# servo.net
KiCad netlist of a schematic drawn in Altium Designer
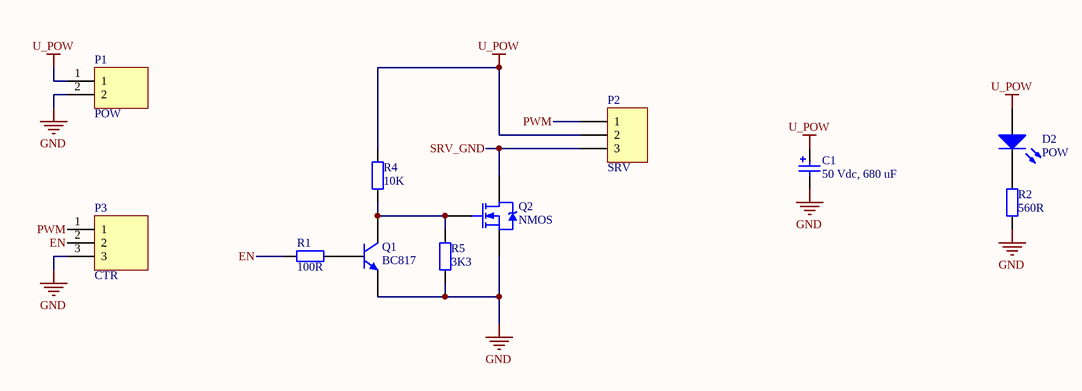
[diagram p0: servo.SchDoc]

(export (version "E")
  (design (tool "Eeschema 10.0.6"))
  (components
    (comp (ref "C1")
      (value "50 Vdc, 680 uF")
      (footprint "WCAP-ATG8_13x20x5")
      (description "WCAP-ATG8 Aluminum Electrolytic Capacitors, 13x20mm, 50 Vdc, 680 uF")
      (fields (field (name "PART NUMBER") "860010678022") (field (name "PUBLISHER") "Wurth Elektronik"))
      (libsource (lib "servo-board") (part "ELKO 860010678022"))
    )
    (comp (ref "D2")
      (value "POW")
      (footprint "FP_0805_LED_RED")
      (description "Typical RED GaAs LED")
      (libsource (lib "hallglib") (part "LED"))
    )
    (comp (ref "P1")
      (value "POW")
      (footprint "FP_CONN2_TAP_254MM_90_EDGE")
      (description "2pin connector")
      (libsource (lib "hallglib") (part "Connector_2pin"))
    )
    (comp (ref "P2")
      (value "SRV")
      (footprint "HDR1X3")
      (description "Header, 3-Pin, Right Angle")
      (fields (field (name "PUBLISHER") "Altium Limited"))
      (libsource (lib "Miscellaneous Connectors") (part "Header 3H"))
    )
    (comp (ref "P3")
      (value "CTR")
      (footprint "FP_CONN3_TAP_254MM_90_EDGE")
      (description "3pin connector")
      (libsource (lib "hallglib") (part "Connector_3pin"))
    )
    (comp (ref "Q1")
      (value "BC817")
      (footprint "FP_SOT23-3")
      (description "NPN General-purpose Transistor")
      (libsource (lib "hallglib") (part "BC817"))
    )
    (comp (ref "Q2") (value "NMOS") (footprint "FP_DPAK-TO252") (libsource (lib "hallglib") (part "NMOS")))
    (comp (ref "R1")
      (value "100R")
      (footprint "FP_0805_RES")
      (description "Resistor")
      (libsource (lib "") (part "RES_1"))
    )
    (comp (ref "R2")
      (value "560R")
      (footprint "FP_0805_RES")
      (description "Resistor")
      (libsource (lib "hallglib") (part "RES"))
    )
    (comp (ref "R4")
      (value "10K")
      (footprint "FP_0805_RES")
      (description "Resistor")
      (libsource (lib "hallglib") (part "RES"))
    )
    (comp (ref "R5")
      (value "3K3")
      (footprint "FP_0805_RES")
      (description "Resistor")
      (libsource (lib "hallglib") (part "RES"))
    )
  )
  (nets
    (net (code "1") (name "/EN") (class "Default")
      (node (ref "P3") (pin "2") (pinfunction "2_2") (pintype "passive"))
      (node (ref "R1") (pin "1") (pinfunction "1_1") (pintype "passive"))
    )
    (net (code "2") (name "/PWM") (class "Default")
      (node (ref "P2") (pin "1") (pinfunction "1_1") (pintype "passive"))
      (node (ref "P3") (pin "1") (pinfunction "1_1") (pintype "passive"))
    )
    (net (code "3") (name "/SRV_GND") (class "Default")
      (node (ref "P2") (pin "3") (pinfunction "3_3") (pintype "passive"))
      (node (ref "Q2") (pin "2") (pinfunction "D_2") (pintype "passive"))
    )
    (net (code "4") (name "GND") (class "Default")
      (node (ref "C1") (pin "2") (pinfunction "N_2") (pintype "passive"))
      (node (ref "P1") (pin "2") (pinfunction "2_2") (pintype "passive"))
      (node (ref "P3") (pin "3") (pinfunction "3_3") (pintype "passive"))
      (node (ref "Q1") (pin "2") (pinfunction "E_2") (pintype "passive"))
      (node (ref "Q2") (pin "3") (pinfunction "S_3") (pintype "passive"))
      (node (ref "R2") (pin "1") (pinfunction "1_1") (pintype "passive"))
      (node (ref "R5") (pin "1") (pinfunction "1_1") (pintype "passive"))
    )
    (net (code "5") (name "Net-(D2-K)") (class "Default")
      (node (ref "D2") (pin "2") (pinfunction "K_2") (pintype "passive"))
      (node (ref "R2") (pin "2") (pinfunction "2_2") (pintype "passive"))
    )
    (net (code "6") (name "Net-(Q1-B)") (class "Default")
      (node (ref "Q1") (pin "1") (pinfunction "B_1") (pintype "passive"))
      (node (ref "R1") (pin "2") (pinfunction "2_2") (pintype "passive"))
    )
    (net (code "7") (name "Net-(Q1-C)") (class "Default")
      (node (ref "Q1") (pin "3") (pinfunction "C_3") (pintype "passive"))
      (node (ref "Q2") (pin "1") (pinfunction "G_1") (pintype "passive"))
      (node (ref "R4") (pin "1") (pinfunction "1_1") (pintype "passive"))
      (node (ref "R5") (pin "2") (pinfunction "2_2") (pintype "passive"))
    )
    (net (code "8") (name "U_POW") (class "Default")
      (node (ref "C1") (pin "1") (pinfunction "P_1") (pintype "passive"))
      (node (ref "D2") (pin "1") (pinfunction "A_1") (pintype "passive"))
      (node (ref "P1") (pin "1") (pinfunction "1_1") (pintype "passive"))
      (node (ref "P2") (pin "2") (pinfunction "2_2") (pintype "passive"))
      (node (ref "R4") (pin "2") (pinfunction "2_2") (pintype "passive"))
    )
  )
)
